# Sheet2.net
KiCad netlist of a schematic drawn in Altium Designer
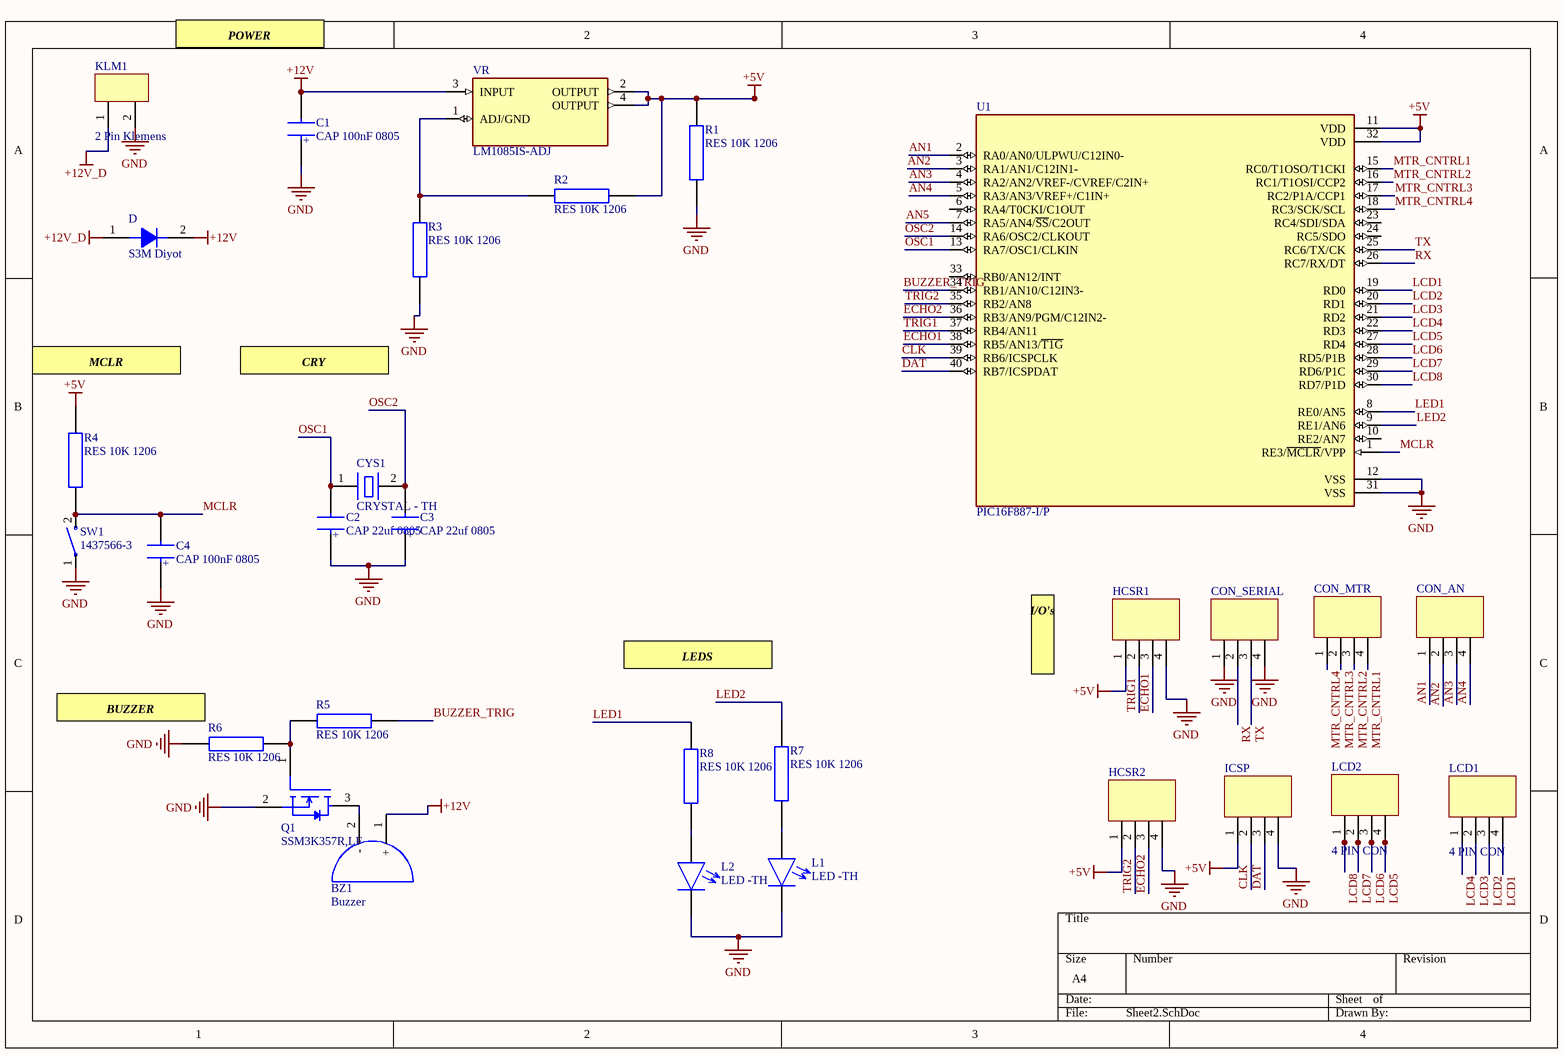
[diagram p0: Sheet2.SchDoc]

(export (version "E")
  (design (tool "Eeschema 10.0.6"))
  (components
    (comp (ref "BZ1")
      (value "Buzzer")
      (footprint "CMI-9605IC")
      (fields (field (name "DESIGNED BY") "Ahmet Azboy"))
      (libsource (lib "Udemy_Schlib1") (part "BUZZER"))
    )
    (comp (ref "C1")
      (value "CAP 100nF 0805")
      (footprint "CAP_805")
      (description "0805 smd")
      (libsource (lib "Udemy_Schlib1") (part "CAP 100nF 0805"))
    )
    (comp (ref "C2")
      (value "CAP 22uf 0805")
      (footprint "CAP_805")
      (description "0805 smd")
      (libsource (lib "Udemy_Schlib1") (part "CAP 22uf 0805"))
    )
    (comp (ref "C3")
      (value "CAP 22uf 0805")
      (footprint "CAP_805")
      (description "0805 smd")
      (libsource (lib "Udemy_Schlib1") (part "CAP 22uf 0805"))
    )
    (comp (ref "C4")
      (value "CAP 100nF 0805")
      (footprint "CAP_805")
      (description "0805 smd")
      (libsource (lib "Udemy_Schlib1") (part "CAP 100nF 0805"))
    )
    (comp (ref "CON_AN")
      (value "4 PIN CON")
      (footprint "4 PIN 2.54MM")
      (description "2.54mm vertical connector")
      (libsource (lib "Udemy_Schlib1") (part "4 PIN CON"))
    )
    (comp (ref "CON_MTR")
      (value "4 PIN CON")
      (footprint "4 PIN 2.54MM")
      (description "2.54mm vertical connector")
      (libsource (lib "Udemy_Schlib1") (part "4 PIN CON"))
    )
    (comp (ref "CON_SERIAL")
      (value "4 PIN CON")
      (footprint "4 PIN 2.54MM")
      (description "2.54mm vertical connector")
      (libsource (lib "Udemy_Schlib1") (part "4 PIN CON"))
    )
    (comp (ref "CYS1")
      (value "CRYSTAL - TH")
      (footprint "Kristal - HC-49Us -th")
      (description "Smd tipi kristal")
      (libsource (lib "Schlib") (part "CRYSTAL - TH"))
    )
    (comp (ref "D")
      (value "S3M Diyot")
      (footprint "DO214AA")
      (fields (field (name "VOLTAGE") "1000V"))
      (libsource (lib "Udemy_Schlib1") (part "S3M Diyot"))
    )
    (comp (ref "HCSR1")
      (value "4 PIN CON")
      (footprint "4 PIN 2.54MM")
      (description "2.54mm vertical connector")
      (libsource (lib "Udemy_Schlib1") (part "4 PIN CON"))
    )
    (comp (ref "HCSR2")
      (value "4 PIN CON")
      (footprint "4 PIN 2.54MM")
      (description "2.54mm vertical connector")
      (libsource (lib "Udemy_Schlib1") (part "4 PIN CON"))
    )
    (comp (ref "ICSP")
      (value "4 PIN CON")
      (footprint "4 PIN 2.54MM")
      (description "2.54mm vertical connector")
      (libsource (lib "Udemy_Schlib1") (part "4 PIN CON"))
    )
    (comp (ref "KLM1")
      (value "2 Pin Klemens")
      (footprint "5.08mm-2 pin")
      (description "5.08mm 2 pin klemens")
      (libsource (lib "Udemy_Schlib1") (part "2 Pin Klemens"))
    )
    (comp (ref "L1") (value "LED -TH") (libsource (lib "Schlib") (part "LED -TH")))
    (comp (ref "L2") (value "LED -TH") (libsource (lib "Schlib") (part "LED -TH")))
    (comp (ref "LCD1")
      (value "4 PIN CON")
      (footprint "4 PIN 2.54MM")
      (description "2.54mm vertical connector")
      (libsource (lib "Udemy_Schlib1") (part "4 PIN CON"))
    )
    (comp (ref "LCD2")
      (value "4 PIN CON")
      (footprint "4 PIN 2.54MM")
      (description "2.54mm vertical connector")
      (libsource (lib "Udemy_Schlib1") (part "4 PIN CON"))
    )
    (comp (ref "Q1")
      (value "SSM3K357R,LF")
      (footprint "SOT-23F")
      (description "Trans MOSFET N-CH Si 60V 0.65A Automotive 3-Pin SOT-23F T/R")
      (fields (field (name "MANUFACTURER") "Toshiba") (field (name "DESIGNED BY") "Ahmet Azboy"))
      (libsource (lib "Udemy_Schlib1") (part "SSM3K357R,LF"))
    )
    (comp (ref "R1")
      (value "RES 10K 1206")
      (footprint "RES_1206")
      (libsource (lib "Udemy_Schlib1") (part "RES 10K 1206"))
    )
    (comp (ref "R2")
      (value "RES 10K 1206")
      (footprint "RES_1206")
      (libsource (lib "Udemy_Schlib1") (part "RES 10K 1206"))
    )
    (comp (ref "R3")
      (value "RES 10K 1206")
      (footprint "RES_1206")
      (libsource (lib "Udemy_Schlib1") (part "RES 10K 1206"))
    )
    (comp (ref "R4")
      (value "RES 10K 1206")
      (footprint "RES_1206")
      (libsource (lib "Udemy_Schlib1") (part "RES 10K 1206"))
    )
    (comp (ref "R5")
      (value "RES 10K 1206")
      (footprint "RES_1206")
      (libsource (lib "Udemy_Schlib1") (part "RES 10K 1206"))
    )
    (comp (ref "R6")
      (value "RES 10K 1206")
      (footprint "RES_1206")
      (libsource (lib "Udemy_Schlib1") (part "RES 10K 1206"))
    )
    (comp (ref "R7")
      (value "RES 10K 1206")
      (footprint "RES_1206")
      (libsource (lib "Udemy_Schlib1") (part "RES 10K 1206"))
    )
    (comp (ref "R8")
      (value "RES 10K 1206")
      (footprint "RES_1206")
      (libsource (lib "Udemy_Schlib1") (part "RES 10K 1206"))
    )
    (comp (ref "SW1")
      (value "1437566-3")
      (footprint "SW_1437566-3")
      (description "Switch Tactile OFF (ON) SPST Rectangular Button Gull Wing 0.05A 12VDC SMD Loose Piece")
      (libsource (lib "Schlib") (part "1437566-3"))
    )
    (comp (ref "U1")
      (value "PIC16F887-I/P")
      (footprint "PIC_ZIF_SOCKET")
      (fields (field (name "MF") "Microchip"))
      (libsource (lib "Schlib") (part "PIC16F887-I/P"))
    )
    (comp (ref "VR")
      (value "LM1085IS-ADJ")
      (footprint "TO254P1524X483-4N")
      (description "3-A, 29-V, linear voltage regulator 3-DDPAK/TO-263")
      (fields (field (name "MF") "Texas Instruments"))
      (libsource (lib "Schlib") (part "LM1085IS-ADJ"))
    )
  )
  (nets
    (net (code "1") (name "+5V") (class "Default")
      (node (ref "HCSR1") (pin "1") (pintype "passive"))
      (node (ref "HCSR2") (pin "1") (pintype "passive"))
      (node (ref "ICSP") (pin "1") (pintype "passive"))
      (node (ref "R1") (pin "1") (pintype "passive"))
      (node (ref "R2") (pin "1") (pintype "passive"))
      (node (ref "R4") (pin "2") (pintype "passive"))
      (node (ref "U1") (pin "11") (pinfunction "VDD_11") (pintype "power_in"))
      (node (ref "U1") (pin "32") (pinfunction "VDD_32") (pintype "power_in"))
      (node (ref "VR") (pin "2") (pinfunction "OUTPUT_2") (pintype "output"))
      (node (ref "VR") (pin "4") (pinfunction "OUTPUT_4") (pintype "output"))
    )
    (net (code "2") (name "+12V") (class "Default")
      (node (ref "BZ1") (pin "1") (pinfunction "+_1") (pintype "passive"))
      (node (ref "C1") (pin "2") (pinfunction "2_2") (pintype "passive"))
      (node (ref "D") (pin "2") (pintype "passive"))
      (node (ref "VR") (pin "3") (pinfunction "INPUT_3") (pintype "input"))
    )
    (net (code "3") (name "+12V_D") (class "Default")
      (node (ref "D") (pin "1") (pintype "passive"))
      (node (ref "KLM1") (pin "1") (pintype "passive"))
    )
    (net (code "4") (name "/AN1") (class "Default")
      (node (ref "CON_AN") (pin "1") (pintype "passive"))
      (node (ref "U1") (pin "2") (pinfunction "RA0/AN0/ULPWU/C12IN0-_2") (pintype "bidirectional"))
    )
    (net (code "5") (name "/AN2") (class "Default")
      (node (ref "CON_AN") (pin "2") (pintype "passive"))
      (node (ref "U1") (pin "3") (pinfunction "RA1/AN1/C12IN1-_3") (pintype "bidirectional"))
    )
    (net (code "6") (name "/AN3") (class "Default")
      (node (ref "CON_AN") (pin "3") (pintype "passive"))
      (node (ref "U1") (pin "4") (pinfunction "RA2/AN2/VREF-/CVREF/C2IN+_4") (pintype "bidirectional"))
    )
    (net (code "7") (name "/AN4") (class "Default")
      (node (ref "CON_AN") (pin "4") (pintype "passive"))
      (node (ref "U1") (pin "5") (pinfunction "RA3/AN3/VREF+/C1IN+_5") (pintype "bidirectional"))
    )
    (net (code "8") (name "/AN5") (class "Default")
      (node (ref "U1") (pin "7") (pinfunction "RA5/AN4/~{SS}/C2OUT_7") (pintype "bidirectional"))
    )
    (net (code "9") (name "/BUZZER_TRIG") (class "Default")
      (node (ref "R5") (pin "1") (pintype "passive"))
      (node (ref "U1") (pin "34") (pinfunction "RB1/AN10/C12IN3-_34") (pintype "bidirectional"))
    )
    (net (code "10") (name "/CLK") (class "Default")
      (node (ref "ICSP") (pin "2") (pintype "passive"))
      (node (ref "U1") (pin "39") (pinfunction "RB6/ICSPCLK_39") (pintype "bidirectional"))
    )
    (net (code "11") (name "/DAT") (class "Default")
      (node (ref "ICSP") (pin "3") (pintype "passive"))
      (node (ref "U1") (pin "40") (pinfunction "RB7/ICSPDAT_40") (pintype "bidirectional"))
    )
    (net (code "12") (name "/ECHO1") (class "Default")
      (node (ref "HCSR1") (pin "3") (pintype "passive"))
      (node (ref "U1") (pin "38") (pinfunction "RB5/AN13/~{T1G}_38") (pintype "bidirectional"))
    )
    (net (code "13") (name "/ECHO2") (class "Default")
      (node (ref "HCSR2") (pin "3") (pintype "passive"))
      (node (ref "U1") (pin "36") (pinfunction "RB3/AN9/PGM/C12IN2-_36") (pintype "bidirectional"))
    )
    (net (code "14") (name "/LCD1") (class "Default")
      (node (ref "LCD1") (pin "4") (pintype "passive"))
      (node (ref "U1") (pin "19") (pinfunction "RD0_19") (pintype "bidirectional"))
    )
    (net (code "15") (name "/LCD2") (class "Default")
      (node (ref "LCD1") (pin "3") (pintype "passive"))
      (node (ref "U1") (pin "20") (pinfunction "RD1_20") (pintype "bidirectional"))
    )
    (net (code "16") (name "/LCD3") (class "Default")
      (node (ref "LCD1") (pin "2") (pintype "passive"))
      (node (ref "U1") (pin "21") (pinfunction "RD2_21") (pintype "bidirectional"))
    )
    (net (code "17") (name "/LCD4") (class "Default")
      (node (ref "LCD1") (pin "1") (pintype "passive"))
      (node (ref "U1") (pin "22") (pinfunction "RD3_22") (pintype "bidirectional"))
    )
    (net (code "18") (name "/LCD5") (class "Default")
      (node (ref "LCD2") (pin "4") (pintype "passive"))
      (node (ref "U1") (pin "27") (pinfunction "RD4_27") (pintype "bidirectional"))
    )
    (net (code "19") (name "/LCD6") (class "Default")
      (node (ref "LCD2") (pin "3") (pintype "passive"))
      (node (ref "U1") (pin "28") (pinfunction "RD5/P1B_28") (pintype "bidirectional"))
    )
    (net (code "20") (name "/LCD7") (class "Default")
      (node (ref "LCD2") (pin "2") (pintype "passive"))
      (node (ref "U1") (pin "29") (pinfunction "RD6/P1C_29") (pintype "bidirectional"))
    )
    (net (code "21") (name "/LCD8") (class "Default")
      (node (ref "LCD2") (pin "1") (pintype "passive"))
      (node (ref "U1") (pin "30") (pinfunction "RD7/P1D_30") (pintype "bidirectional"))
    )
    (net (code "22") (name "/LED1") (class "Default")
      (node (ref "R8") (pin "2") (pintype "passive"))
      (node (ref "U1") (pin "8") (pinfunction "RE0/AN5_8") (pintype "bidirectional"))
    )
    (net (code "23") (name "/LED2") (class "Default")
      (node (ref "R7") (pin "2") (pintype "passive"))
      (node (ref "U1") (pin "9") (pinfunction "RE1/AN6_9") (pintype "bidirectional"))
    )
    (net (code "24") (name "/MCLR") (class "Default")
      (node (ref "C4") (pin "2") (pinfunction "2_2") (pintype "passive"))
      (node (ref "R4") (pin "1") (pintype "passive"))
      (node (ref "SW1") (pin "2") (pinfunction "2_2") (pintype "passive"))
      (node (ref "U1") (pin "1") (pinfunction "RE3/~{MCLR}/VPP_1") (pintype "input"))
    )
    (net (code "25") (name "/MTR_CNTRL1") (class "Default")
      (node (ref "CON_MTR") (pin "4") (pintype "passive"))
      (node (ref "U1") (pin "15") (pinfunction "RC0/T1OSO/T1CKI_15") (pintype "bidirectional"))
    )
    (net (code "26") (name "/MTR_CNTRL2") (class "Default")
      (node (ref "CON_MTR") (pin "3") (pintype "passive"))
      (node (ref "U1") (pin "16") (pinfunction "RC1/T1OSI/CCP2_16") (pintype "bidirectional"))
    )
    (net (code "27") (name "/MTR_CNTRL3") (class "Default")
      (node (ref "CON_MTR") (pin "2") (pintype "passive"))
      (node (ref "U1") (pin "17") (pinfunction "RC2/P1A/CCP1_17") (pintype "bidirectional"))
    )
    (net (code "28") (name "/MTR_CNTRL4") (class "Default")
      (node (ref "CON_MTR") (pin "1") (pintype "passive"))
      (node (ref "U1") (pin "18") (pinfunction "RC3/SCK/SCL_18") (pintype "bidirectional"))
    )
    (net (code "29") (name "/OSC1") (class "Default")
      (node (ref "C2") (pin "2") (pinfunction "2_2") (pintype "passive"))
      (node (ref "CYS1") (pin "1") (pintype "passive"))
      (node (ref "U1") (pin "13") (pinfunction "RA7/OSC1/CLKIN_13") (pintype "bidirectional"))
    )
    (net (code "30") (name "/OSC2") (class "Default")
      (node (ref "C3") (pin "2") (pinfunction "2_2") (pintype "passive"))
      (node (ref "CYS1") (pin "2") (pintype "passive"))
      (node (ref "U1") (pin "14") (pinfunction "RA6/OSC2/CLKOUT_14") (pintype "bidirectional"))
    )
    (net (code "31") (name "/RX") (class "Default")
      (node (ref "CON_SERIAL") (pin "2") (pintype "passive"))
      (node (ref "U1") (pin "26") (pinfunction "RC7/RX/DT_26") (pintype "bidirectional"))
    )
    (net (code "32") (name "/TRIG1") (class "Default")
      (node (ref "HCSR1") (pin "2") (pintype "passive"))
      (node (ref "U1") (pin "37") (pinfunction "RB4/AN11_37") (pintype "bidirectional"))
    )
    (net (code "33") (name "/TRIG2") (class "Default")
      (node (ref "HCSR2") (pin "2") (pintype "passive"))
      (node (ref "U1") (pin "35") (pinfunction "RB2/AN8_35") (pintype "bidirectional"))
    )
    (net (code "34") (name "/TX") (class "Default")
      (node (ref "CON_SERIAL") (pin "3") (pintype "passive"))
      (node (ref "U1") (pin "25") (pinfunction "RC6/TX/CK_25") (pintype "bidirectional"))
    )
    (net (code "35") (name "GND") (class "Default")
      (node (ref "C1") (pin "1") (pinfunction "1_1") (pintype "passive"))
      (node (ref "C2") (pin "1") (pinfunction "1_1") (pintype "passive"))
      (node (ref "C3") (pin "1") (pinfunction "1_1") (pintype "passive"))
      (node (ref "C4") (pin "1") (pinfunction "1_1") (pintype "passive"))
      (node (ref "CON_SERIAL") (pin "1") (pintype "passive"))
      (node (ref "CON_SERIAL") (pin "4") (pintype "passive"))
      (node (ref "HCSR1") (pin "4") (pintype "passive"))
      (node (ref "HCSR2") (pin "4") (pintype "passive"))
      (node (ref "ICSP") (pin "4") (pintype "passive"))
      (node (ref "KLM1") (pin "2") (pintype "passive"))
      (node (ref "L1") (pin "2") (pintype "passive"))
      (node (ref "L2") (pin "2") (pintype "passive"))
      (node (ref "Q1") (pin "2") (pinfunction "S_2") (pintype "passive"))
      (node (ref "R1") (pin "2") (pintype "passive"))
      (node (ref "R3") (pin "1") (pintype "passive"))
      (node (ref "R6") (pin "2") (pintype "passive"))
      (node (ref "SW1") (pin "1") (pinfunction "1_1") (pintype "passive"))
      (node (ref "U1") (pin "12") (pinfunction "VSS_12") (pintype "power_in"))
      (node (ref "U1") (pin "31") (pinfunction "VSS_31") (pintype "power_in"))
    )
    (net (code "36") (name "Net-(BZ1--)") (class "Default")
      (node (ref "BZ1") (pin "2") (pinfunction "-_2") (pintype "passive"))
      (node (ref "Q1") (pin "3") (pinfunction "D_3") (pintype "passive"))
    )
    (net (code "37") (name "Net-(L1-Pad1)") (class "Default")
      (node (ref "L1") (pin "1") (pintype "passive"))
      (node (ref "R7") (pin "1") (pintype "passive"))
    )
    (net (code "38") (name "Net-(L2-Pad1)") (class "Default")
      (node (ref "L2") (pin "1") (pintype "passive"))
      (node (ref "R8") (pin "1") (pintype "passive"))
    )
    (net (code "39") (name "Net-(Q1-G)") (class "Default")
      (node (ref "Q1") (pin "1") (pinfunction "G_1") (pintype "passive"))
      (node (ref "R5") (pin "2") (pintype "passive"))
      (node (ref "R6") (pin "1") (pintype "passive"))
    )
    (net (code "40") (name "Net-(VR-ADJ{slash}GND)") (class "Default")
      (node (ref "R2") (pin "2") (pintype "passive"))
      (node (ref "R3") (pin "2") (pintype "passive"))
      (node (ref "VR") (pin "1") (pinfunction "ADJ/GND_1") (pintype "bidirectional"))
    )
    (net (code "41") (name "unconnected-(U1-RA4{slash}T0CKI{slash}C1OUT-Pad6)") (class "Default")
      (node (ref "U1") (pin "6") (pinfunction "RA4/T0CKI/C1OUT_6") (pintype "bidirectional"))
    )
    (net (code "42") (name "unconnected-(U1-RB0{slash}AN12{slash}INT-Pad33)") (class "Default")
      (node (ref "U1") (pin "33") (pinfunction "RB0/AN12/INT_33") (pintype "bidirectional"))
    )
    (net (code "43") (name "unconnected-(U1-RC4{slash}SDI{slash}SDA-Pad23)") (class "Default")
      (node (ref "U1") (pin "23") (pinfunction "RC4/SDI/SDA_23") (pintype "bidirectional"))
    )
    (net (code "44") (name "unconnected-(U1-RC5{slash}SDO-Pad24)") (class "Default")
      (node (ref "U1") (pin "24") (pinfunction "RC5/SDO_24") (pintype "bidirectional"))
    )
    (net (code "45") (name "unconnected-(U1-RE2{slash}AN7-Pad10)") (class "Default")
      (node (ref "U1") (pin "10") (pinfunction "RE2/AN7_10") (pintype "bidirectional"))
    )
  )
)
